# Becca_Sap_Flow_Power_Board_v1_2.net
KiCad netlist of a schematic drawn in EAGLE
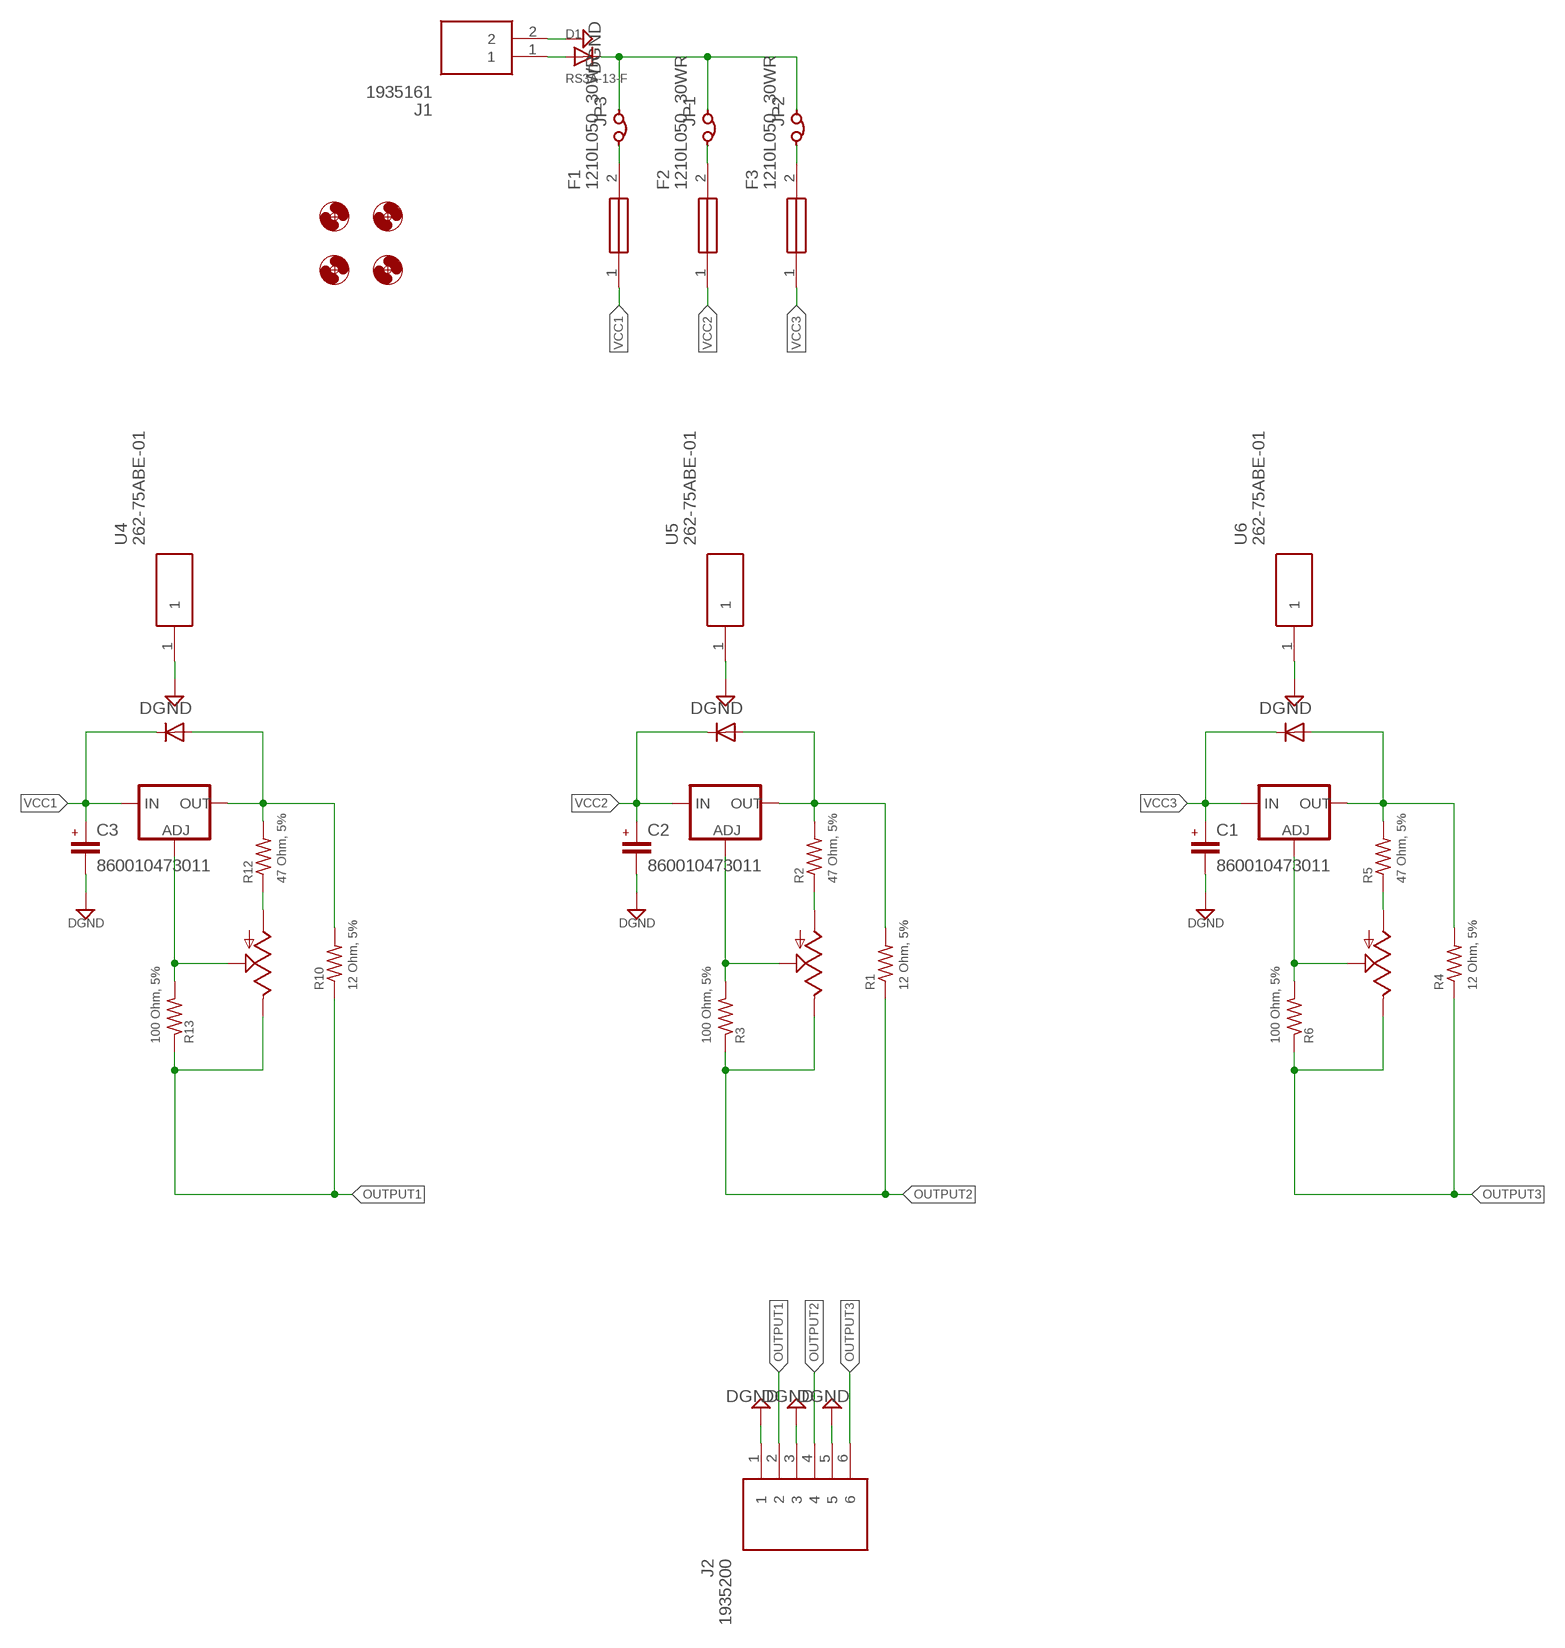
[diagram p0: schematic, sheet 1]

(export (version "E")
  (design (tool "Eeschema 10.0.6"))
  (components
    (comp (ref "C1")
      (value "860010473011")
      (footprint "eagle-import:CAPPRD250W52D630H1250")
      (fields (field (name "MOUSER_PART_NUMBER") "710-860010473011"))
      (libsource (lib "eagle-import") (part "860010473011"))
    )
    (comp (ref "C2")
      (value "860010473011")
      (footprint "eagle-import:CAPPRD250W52D630H1250")
      (fields (field (name "MOUSER_PART_NUMBER") "710-860010473011"))
      (libsource (lib "eagle-import") (part "860010473011"))
    )
    (comp (ref "C3")
      (value "860010473011")
      (footprint "eagle-import:CAPPRD250W52D630H1250")
      (fields (field (name "MOUSER_PART_NUMBER") "710-860010473011"))
      (libsource (lib "eagle-import") (part "860010473011"))
    )
    (comp (ref "D1")
      (value "RS3A-13-F")
      (footprint "eagle-import:DIOM7959X250N")
      (fields (field (name "MOUSER_PART_NUMBER") "621-RS3A-13-F"))
      (libsource (lib "eagle-import") (part "RS3A-13-F"))
    )
    (comp (ref "D3")
      (value "S1A")
      (footprint "eagle-import:DIOM5027X250N")
      (fields (field (name "MOUSER_PART_NUMBER") "637-S1A"))
      (libsource (lib "eagle-import") (part "S1A"))
    )
    (comp (ref "D4")
      (value "S1A")
      (footprint "eagle-import:DIOM5027X250N")
      (fields (field (name "MOUSER_PART_NUMBER") "637-S1A"))
      (libsource (lib "eagle-import") (part "S1A"))
    )
    (comp (ref "D6")
      (value "S1A")
      (footprint "eagle-import:DIOM5027X250N")
      (fields (field (name "MOUSER_PART_NUMBER") "637-S1A"))
      (libsource (lib "eagle-import") (part "S1A"))
    )
    (comp (ref "F1")
      (value "1210L050_30WR")
      (footprint "eagle-import:THRMC3226X125N")
      (fields
        (field (name "MANUFACTURER_PART_NUMBER") "1210L050/30WR")
        (field (name "MOUSER_PART_NUMBER") "576-1210L050/30WR")
      )
      (libsource (lib "eagle-import") (part "1210L050_30WR"))
    )
    (comp (ref "F2")
      (value "1210L050_30WR")
      (footprint "eagle-import:THRMC3226X125N")
      (fields
        (field (name "MANUFACTURER_PART_NUMBER") "1210L050/30WR")
        (field (name "MOUSER_PART_NUMBER") "576-1210L050/30WR")
      )
      (libsource (lib "eagle-import") (part "1210L050_30WR"))
    )
    (comp (ref "F3")
      (value "1210L050_30WR")
      (footprint "eagle-import:THRMC3226X125N")
      (fields
        (field (name "MANUFACTURER_PART_NUMBER") "1210L050/30WR")
        (field (name "MOUSER_PART_NUMBER") "576-1210L050/30WR")
      )
      (libsource (lib "eagle-import") (part "1210L050_30WR"))
    )
    (comp (ref "J1")
      (value "1935161")
      (footprint "eagle-import:1935161")
      (fields (field (name "MOUSER_PART_NUMBER") "651-1935161"))
      (libsource (lib "eagle-import") (part "1935161"))
    )
    (comp (ref "J2")
      (value "1935200")
      (footprint "eagle-import:1935200")
      (fields (field (name "MOUSER_PART_NUMBER") "651-1935200"))
      (libsource (lib "eagle-import") (part "1935200"))
    )
    (comp (ref "JP1")
      (value "JUMPER")
      (footprint "eagle-import:HDR2X1")
      (libsource (lib "eagle-import") (part "JUMPER"))
    )
    (comp (ref "JP2")
      (value "JUMPER")
      (footprint "eagle-import:HDR2X1")
      (libsource (lib "eagle-import") (part "JUMPER"))
    )
    (comp (ref "JP3")
      (value "JUMPER")
      (footprint "eagle-import:HDR2X1")
      (libsource (lib "eagle-import") (part "JUMPER"))
    )
    (comp (ref "R1")
      (value "12 Ohm, 5%")
      (footprint "eagle-import:R1210")
      (libsource (lib "eagle-import") (part "R-US_R1210"))
    )
    (comp (ref "R2")
      (value "47 Ohm, 5%")
      (footprint "eagle-import:R1210")
      (libsource (lib "eagle-import") (part "R-US_R1210"))
    )
    (comp (ref "R3")
      (value "100 Ohm, 5%")
      (footprint "eagle-import:R1210")
      (libsource (lib "eagle-import") (part "R-US_R1210"))
    )
    (comp (ref "R4")
      (value "12 Ohm, 5%")
      (footprint "eagle-import:R1210")
      (libsource (lib "eagle-import") (part "R-US_R1210"))
    )
    (comp (ref "R5")
      (value "47 Ohm, 5%")
      (footprint "eagle-import:R1210")
      (libsource (lib "eagle-import") (part "R-US_R1210"))
    )
    (comp (ref "R6")
      (value "100 Ohm, 5%")
      (footprint "eagle-import:R1210")
      (libsource (lib "eagle-import") (part "R-US_R1210"))
    )
    (comp (ref "R10")
      (value "12 Ohm, 5%")
      (footprint "eagle-import:R1210")
      (libsource (lib "eagle-import") (part "R-US_R1210"))
    )
    (comp (ref "R12")
      (value "47 Ohm, 5%")
      (footprint "eagle-import:R1210")
      (libsource (lib "eagle-import") (part "R-US_R1210"))
    )
    (comp (ref "R13")
      (value "100 Ohm, 5%")
      (footprint "eagle-import:R1210")
      (libsource (lib "eagle-import") (part "R-US_R1210"))
    )
    (comp (ref "U$1")
      (value "MOUNT-HOLE3.0")
      (footprint "eagle-import:3,0")
      (libsource (lib "eagle-import") (part "MOUNT-HOLE3.0"))
    )
    (comp (ref "U$2")
      (value "MOUNT-HOLE3.0")
      (footprint "eagle-import:3,0")
      (libsource (lib "eagle-import") (part "MOUNT-HOLE3.0"))
    )
    (comp (ref "U$3")
      (value "MOUNT-HOLE3.0")
      (footprint "eagle-import:3,0")
      (libsource (lib "eagle-import") (part "MOUNT-HOLE3.0"))
    )
    (comp (ref "U$4")
      (value "MOUNT-HOLE3.0")
      (footprint "eagle-import:3,0")
      (libsource (lib "eagle-import") (part "MOUNT-HOLE3.0"))
    )
    (comp (ref "U1")
      (value "LM317MTG")
      (footprint "eagle-import:TO254P482X997X2018-3P")
      (fields (field (name "MOUSER_PART_NUMBER") "863-LM317MTG"))
      (libsource (lib "eagle-import") (part "LM317MTG"))
    )
    (comp (ref "U2")
      (value "LM317MTG")
      (footprint "eagle-import:TO254P482X997X2018-3P")
      (fields (field (name "MOUSER_PART_NUMBER") "863-LM317MTG"))
      (libsource (lib "eagle-import") (part "LM317MTG"))
    )
    (comp (ref "U3")
      (value "LM317MTG")
      (footprint "eagle-import:TO254P482X997X2018-3P")
      (fields (field (name "MOUSER_PART_NUMBER") "863-LM317MTG"))
      (libsource (lib "eagle-import") (part "LM317MTG"))
    )
    (comp (ref "U4")
      (value "262-75ABE-01")
      (footprint "eagle-import:26275ABE01")
      (fields (field (name "MOUSER_PART_NUMBER") "567-262-75AB-01E"))
      (libsource (lib "eagle-import") (part "262-75ABE-01"))
    )
    (comp (ref "U5")
      (value "262-75ABE-01")
      (footprint "eagle-import:26275ABE01")
      (fields (field (name "MOUSER_PART_NUMBER") "567-262-75AB-01E"))
      (libsource (lib "eagle-import") (part "262-75ABE-01"))
    )
    (comp (ref "U6")
      (value "262-75ABE-01")
      (footprint "eagle-import:26275ABE01")
      (fields (field (name "MOUSER_PART_NUMBER") "567-262-75AB-01E"))
      (libsource (lib "eagle-import") (part "262-75ABE-01"))
    )
    (comp (ref "VR1")
      (value "3296W-1-102RLF")
      (footprint "eagle-import:3296W1102RLF")
      (fields (field (name "MOUSER_PART_NUMBER") "652-3296W-1-102RLF"))
      (libsource (lib "eagle-import") (part "3296W-1-102RLF"))
    )
    (comp (ref "VR2")
      (value "3296W-1-102RLF")
      (footprint "eagle-import:3296W1102RLF")
      (fields (field (name "MOUSER_PART_NUMBER") "652-3296W-1-102RLF"))
      (libsource (lib "eagle-import") (part "3296W-1-102RLF"))
    )
    (comp (ref "VR3")
      (value "3296W-1-102RLF")
      (footprint "eagle-import:3296W1102RLF")
      (fields (field (name "MOUSER_PART_NUMBER") "652-3296W-1-102RLF"))
      (libsource (lib "eagle-import") (part "3296W-1-102RLF"))
    )
  )
  (nets
    (net (code "1") (name "DGND") (class "Default")
      (node (ref "C1") (pin "2") (pinfunction "2_2") (pintype "passive"))
      (node (ref "C2") (pin "2") (pinfunction "2_2") (pintype "passive"))
      (node (ref "C3") (pin "2") (pinfunction "2_2") (pintype "passive"))
      (node (ref "J1") (pin "2") (pinfunction "2_2") (pintype "bidirectional"))
      (node (ref "J2") (pin "1") (pinfunction "1_1") (pintype "bidirectional"))
      (node (ref "J2") (pin "3") (pinfunction "3_3") (pintype "bidirectional"))
      (node (ref "J2") (pin "5") (pinfunction "5_5") (pintype "bidirectional"))
      (node (ref "U4") (pin "1") (pinfunction "1_1") (pintype "bidirectional"))
      (node (ref "U5") (pin "1") (pinfunction "1_1") (pintype "bidirectional"))
      (node (ref "U6") (pin "1") (pinfunction "1_1") (pintype "bidirectional"))
    )
    (net (code "2") (name "Net-(D1-A)") (class "Default")
      (node (ref "D1") (pin "2") (pinfunction "A_2") (pintype "passive"))
      (node (ref "J1") (pin "1") (pinfunction "1_1") (pintype "bidirectional"))
    )
    (net (code "3") (name "Net-(D1-K)") (class "Default")
      (node (ref "D1") (pin "1") (pinfunction "K_1") (pintype "passive"))
      (node (ref "JP1") (pin "1") (pinfunction "1_1") (pintype "passive"))
      (node (ref "JP2") (pin "1") (pinfunction "1_1") (pintype "passive"))
      (node (ref "JP3") (pin "1") (pinfunction "1_1") (pintype "passive"))
    )
    (net (code "4") (name "Net-(D3-A)") (class "Default")
      (node (ref "D3") (pin "2") (pinfunction "A_2") (pintype "passive"))
      (node (ref "R1") (pin "2") (pinfunction "2_2") (pintype "passive"))
      (node (ref "R2") (pin "2") (pinfunction "2_2") (pintype "passive"))
      (node (ref "U2") (pin "2") (pinfunction "OUT_2") (pintype "output"))
    )
    (net (code "5") (name "Net-(D4-A)") (class "Default")
      (node (ref "D4") (pin "2") (pinfunction "A_2") (pintype "passive"))
      (node (ref "R4") (pin "2") (pinfunction "2_2") (pintype "passive"))
      (node (ref "R5") (pin "2") (pinfunction "2_2") (pintype "passive"))
      (node (ref "U3") (pin "2") (pinfunction "OUT_2") (pintype "output"))
    )
    (net (code "6") (name "Net-(D6-A)") (class "Default")
      (node (ref "D6") (pin "2") (pinfunction "A_2") (pintype "passive"))
      (node (ref "R10") (pin "2") (pinfunction "2_2") (pintype "passive"))
      (node (ref "R12") (pin "2") (pinfunction "2_2") (pintype "passive"))
      (node (ref "U1") (pin "2") (pinfunction "OUT_2") (pintype "output"))
    )
    (net (code "7") (name "Net-(F1-Pad2)") (class "Default")
      (node (ref "F1") (pin "2") (pinfunction "2_2") (pintype "bidirectional"))
      (node (ref "JP3") (pin "2") (pinfunction "2_2") (pintype "passive"))
    )
    (net (code "8") (name "Net-(F2-Pad2)") (class "Default")
      (node (ref "F2") (pin "2") (pinfunction "2_2") (pintype "bidirectional"))
      (node (ref "JP1") (pin "2") (pinfunction "2_2") (pintype "passive"))
    )
    (net (code "9") (name "Net-(F3-Pad2)") (class "Default")
      (node (ref "F3") (pin "2") (pinfunction "2_2") (pintype "bidirectional"))
      (node (ref "JP2") (pin "2") (pinfunction "2_2") (pintype "passive"))
    )
    (net (code "10") (name "Net-(U1-ADJ)") (class "Default")
      (node (ref "R13") (pin "2") (pinfunction "2_2") (pintype "passive"))
      (node (ref "U1") (pin "1") (pinfunction "ADJ_1") (pintype "input"))
      (node (ref "VR1") (pin "2") (pinfunction "S_2") (pintype "passive"))
    )
    (net (code "11") (name "Net-(U2-ADJ)") (class "Default")
      (node (ref "R3") (pin "2") (pinfunction "2_2") (pintype "passive"))
      (node (ref "U2") (pin "1") (pinfunction "ADJ_1") (pintype "input"))
      (node (ref "VR2") (pin "2") (pinfunction "S_2") (pintype "passive"))
    )
    (net (code "12") (name "Net-(U3-ADJ)") (class "Default")
      (node (ref "R6") (pin "2") (pinfunction "2_2") (pintype "passive"))
      (node (ref "U3") (pin "1") (pinfunction "ADJ_1") (pintype "input"))
      (node (ref "VR3") (pin "2") (pinfunction "S_2") (pintype "passive"))
    )
    (net (code "13") (name "Net-(VR1-A)") (class "Default")
      (node (ref "R12") (pin "1") (pinfunction "1_1") (pintype "passive"))
      (node (ref "VR1") (pin "1") (pinfunction "A_1") (pintype "passive"))
    )
    (net (code "14") (name "Net-(VR2-A)") (class "Default")
      (node (ref "R2") (pin "1") (pinfunction "1_1") (pintype "passive"))
      (node (ref "VR2") (pin "1") (pinfunction "A_1") (pintype "passive"))
    )
    (net (code "15") (name "Net-(VR3-A)") (class "Default")
      (node (ref "R5") (pin "1") (pinfunction "1_1") (pintype "passive"))
      (node (ref "VR3") (pin "1") (pinfunction "A_1") (pintype "passive"))
    )
    (net (code "16") (name "OUTPUT1") (class "Default")
      (node (ref "J2") (pin "2") (pinfunction "2_2") (pintype "bidirectional"))
      (node (ref "R10") (pin "1") (pinfunction "1_1") (pintype "passive"))
      (node (ref "R13") (pin "1") (pinfunction "1_1") (pintype "passive"))
      (node (ref "VR1") (pin "3") (pinfunction "E_3") (pintype "passive"))
    )
    (net (code "17") (name "OUTPUT2") (class "Default")
      (node (ref "J2") (pin "4") (pinfunction "4_4") (pintype "bidirectional"))
      (node (ref "R1") (pin "1") (pinfunction "1_1") (pintype "passive"))
      (node (ref "R3") (pin "1") (pinfunction "1_1") (pintype "passive"))
      (node (ref "VR2") (pin "3") (pinfunction "E_3") (pintype "passive"))
    )
    (net (code "18") (name "OUTPUT3") (class "Default")
      (node (ref "J2") (pin "6") (pinfunction "6_6") (pintype "bidirectional"))
      (node (ref "R4") (pin "1") (pinfunction "1_1") (pintype "passive"))
      (node (ref "R6") (pin "1") (pinfunction "1_1") (pintype "passive"))
      (node (ref "VR3") (pin "3") (pinfunction "E_3") (pintype "passive"))
    )
    (net (code "19") (name "VCC1") (class "Default")
      (node (ref "C3") (pin "1") (pinfunction "1_1") (pintype "passive"))
      (node (ref "D6") (pin "1") (pinfunction "K_1") (pintype "passive"))
      (node (ref "F1") (pin "1") (pinfunction "1_1") (pintype "bidirectional"))
      (node (ref "U1") (pin "3") (pinfunction "IN_3") (pintype "input"))
    )
    (net (code "20") (name "VCC2") (class "Default")
      (node (ref "C2") (pin "1") (pinfunction "1_1") (pintype "passive"))
      (node (ref "D3") (pin "1") (pinfunction "K_1") (pintype "passive"))
      (node (ref "F2") (pin "1") (pinfunction "1_1") (pintype "bidirectional"))
      (node (ref "U2") (pin "3") (pinfunction "IN_3") (pintype "input"))
    )
    (net (code "21") (name "VCC3") (class "Default")
      (node (ref "C1") (pin "1") (pinfunction "1_1") (pintype "passive"))
      (node (ref "D4") (pin "1") (pinfunction "K_1") (pintype "passive"))
      (node (ref "F3") (pin "1") (pinfunction "1_1") (pintype "bidirectional"))
      (node (ref "U3") (pin "3") (pinfunction "IN_3") (pintype "input"))
    )
  )
)
